# THERMO.net
KiCad netlist of a schematic drawn in Altium Designer
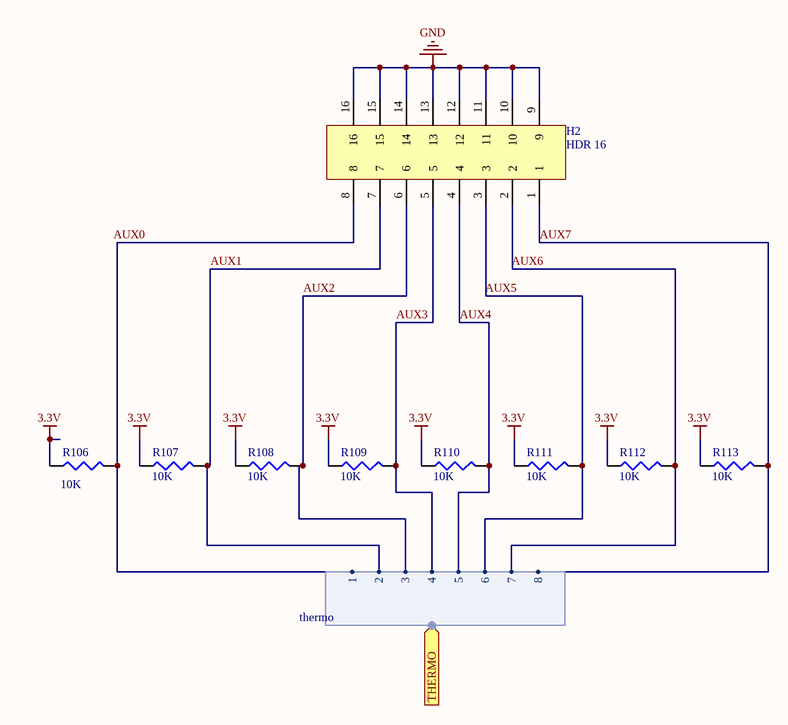
[diagram p0: THERMO.SchDoc]

(export (version "E")
  (design (tool "Eeschema 10.0.6"))
  (components
    (comp (ref "H2")
      (value "HDR 16")
      (footprint "THERMO HDR")
      (fields (field (name "MANUFACTURER") "Molex") (field (name "MANUFACTURER PART NUMBER") "0430451601"))
      (libsource (lib "parts") (part "HDR 16"))
    )
    (comp (ref "R106")
      (value "10K")
      (footprint "0603 RES")
      (description "Resistor")
      (fields
        (field (name "MANUFACTURER") "Vishay")
        (field (name "MANUFACTURER PART NUMBER") "CRCW060310K0FKEA")
        (field (name "PUBLISHER") "Altium Limited")
      )
      (libsource (lib "Miscellaneous Devices") (part "Res3"))
    )
    (comp (ref "R107")
      (value "10K")
      (footprint "0603 RES")
      (description "Resistor")
      (fields
        (field (name "MANUFACTURER") "Vishay")
        (field (name "MANUFACTURER PART NUMBER") "CRCW060310K0FKEA")
        (field (name "PUBLISHER") "Altium Limited")
      )
      (libsource (lib "Miscellaneous Devices") (part "Res3"))
    )
    (comp (ref "R108")
      (value "10K")
      (footprint "0603 RES")
      (description "Resistor")
      (fields
        (field (name "MANUFACTURER") "Vishay")
        (field (name "MANUFACTURER PART NUMBER") "CRCW060310K0FKEA")
        (field (name "PUBLISHER") "Altium Limited")
      )
      (libsource (lib "Miscellaneous Devices") (part "Res3"))
    )
    (comp (ref "R109")
      (value "10K")
      (footprint "0603 RES")
      (description "Resistor")
      (fields
        (field (name "MANUFACTURER") "Vishay")
        (field (name "MANUFACTURER PART NUMBER") "CRCW060310K0FKEA")
        (field (name "PUBLISHER") "Altium Limited")
      )
      (libsource (lib "Miscellaneous Devices") (part "Res3"))
    )
    (comp (ref "R110")
      (value "10K")
      (footprint "0603 RES")
      (description "Resistor")
      (fields
        (field (name "MANUFACTURER") "Vishay")
        (field (name "MANUFACTURER PART NUMBER") "CRCW060310K0FKEA")
        (field (name "PUBLISHER") "Altium Limited")
      )
      (libsource (lib "Miscellaneous Devices") (part "Res3"))
    )
    (comp (ref "R111")
      (value "10K")
      (footprint "0603 RES")
      (description "Resistor")
      (fields
        (field (name "MANUFACTURER") "Vishay")
        (field (name "MANUFACTURER PART NUMBER") "CRCW060310K0FKEA")
        (field (name "PUBLISHER") "Altium Limited")
      )
      (libsource (lib "Miscellaneous Devices") (part "Res3"))
    )
    (comp (ref "R112")
      (value "10K")
      (footprint "0603 RES")
      (description "Resistor")
      (fields
        (field (name "MANUFACTURER") "Vishay")
        (field (name "MANUFACTURER PART NUMBER") "CRCW060310K0FKEA")
        (field (name "PUBLISHER") "Altium Limited")
      )
      (libsource (lib "Miscellaneous Devices") (part "Res3"))
    )
    (comp (ref "R113")
      (value "10K")
      (footprint "0603 RES")
      (description "Resistor")
      (fields
        (field (name "MANUFACTURER") "Vishay")
        (field (name "MANUFACTURER PART NUMBER") "CRCW060310K0FKEA")
        (field (name "PUBLISHER") "Altium Limited")
      )
      (libsource (lib "Miscellaneous Devices") (part "Res3"))
    )
  )
  (nets
    (net (code "3") (name "/AUX1") (class "Default")
      (node (ref "H2") (pin "7") (pinfunction "7_7") (pintype "passive"))
      (node (ref "R107") (pin "2") (pinfunction "2_2") (pintype "passive"))
    )
    (net (code "4") (name "/AUX2") (class "Default")
      (node (ref "H2") (pin "6") (pinfunction "6_6") (pintype "passive"))
      (node (ref "R108") (pin "2") (pinfunction "2_2") (pintype "passive"))
    )
    (net (code "5") (name "/AUX3") (class "Default")
      (node (ref "H2") (pin "5") (pinfunction "5_5") (pintype "passive"))
      (node (ref "R109") (pin "2") (pinfunction "2_2") (pintype "passive"))
    )
    (net (code "6") (name "/AUX4") (class "Default")
      (node (ref "H2") (pin "4") (pinfunction "4_4") (pintype "passive"))
      (node (ref "R110") (pin "2") (pinfunction "2_2") (pintype "passive"))
    )
    (net (code "9") (name "/AUX7") (class "Default")
      (node (ref "H2") (pin "1") (pinfunction "1_1") (pintype "passive"))
      (node (ref "R113") (pin "2") (pinfunction "2_2") (pintype "passive"))
    )
    (net (code "11") (name "3.3V") (class "Default")
      (node (ref "R106") (pin "1") (pinfunction "1_1") (pintype "passive"))
      (node (ref "R107") (pin "1") (pinfunction "1_1") (pintype "passive"))
      (node (ref "R108") (pin "1") (pinfunction "1_1") (pintype "passive"))
      (node (ref "R109") (pin "1") (pinfunction "1_1") (pintype "passive"))
      (node (ref "R110") (pin "1") (pinfunction "1_1") (pintype "passive"))
      (node (ref "R111") (pin "1") (pinfunction "1_1") (pintype "passive"))
      (node (ref "R112") (pin "1") (pinfunction "1_1") (pintype "passive"))
      (node (ref "R113") (pin "1") (pinfunction "1_1") (pintype "passive"))
    )
    (net (code "12") (name "GND") (class "Default")
      (node (ref "H2") (pin "10") (pinfunction "10_10") (pintype "passive"))
      (node (ref "H2") (pin "11") (pinfunction "11_11") (pintype "passive"))
      (node (ref "H2") (pin "12") (pinfunction "12_12") (pintype "passive"))
      (node (ref "H2") (pin "13") (pinfunction "13_13") (pintype "passive"))
      (node (ref "H2") (pin "14") (pinfunction "14_14") (pintype "passive"))
      (node (ref "H2") (pin "15") (pinfunction "15_15") (pintype "passive"))
      (node (ref "H2") (pin "16") (pinfunction "16_16") (pintype "passive"))
      (node (ref "H2") (pin "9") (pinfunction "9_9") (pintype "passive"))
    )
    (net (code "13") (name "Net-(H2-Pad2)") (class "Default")
      (node (ref "H2") (pin "2") (pinfunction "2_2") (pintype "passive"))
      (node (ref "R112") (pin "2") (pinfunction "2_2") (pintype "passive"))
    )
    (net (code "14") (name "Net-(H2-Pad3)") (class "Default")
      (node (ref "H2") (pin "3") (pinfunction "3_3") (pintype "passive"))
      (node (ref "R111") (pin "2") (pinfunction "2_2") (pintype "passive"))
    )
    (net (code "15") (name "Net-(H2-Pad8)") (class "Default")
      (node (ref "H2") (pin "8") (pinfunction "8_8") (pintype "passive"))
      (node (ref "R106") (pin "2") (pinfunction "2_2") (pintype "passive"))
    )
  )
)
